# SelfBus_DAP_Debugger.net
KiCad netlist of a schematic drawn in EAGLE
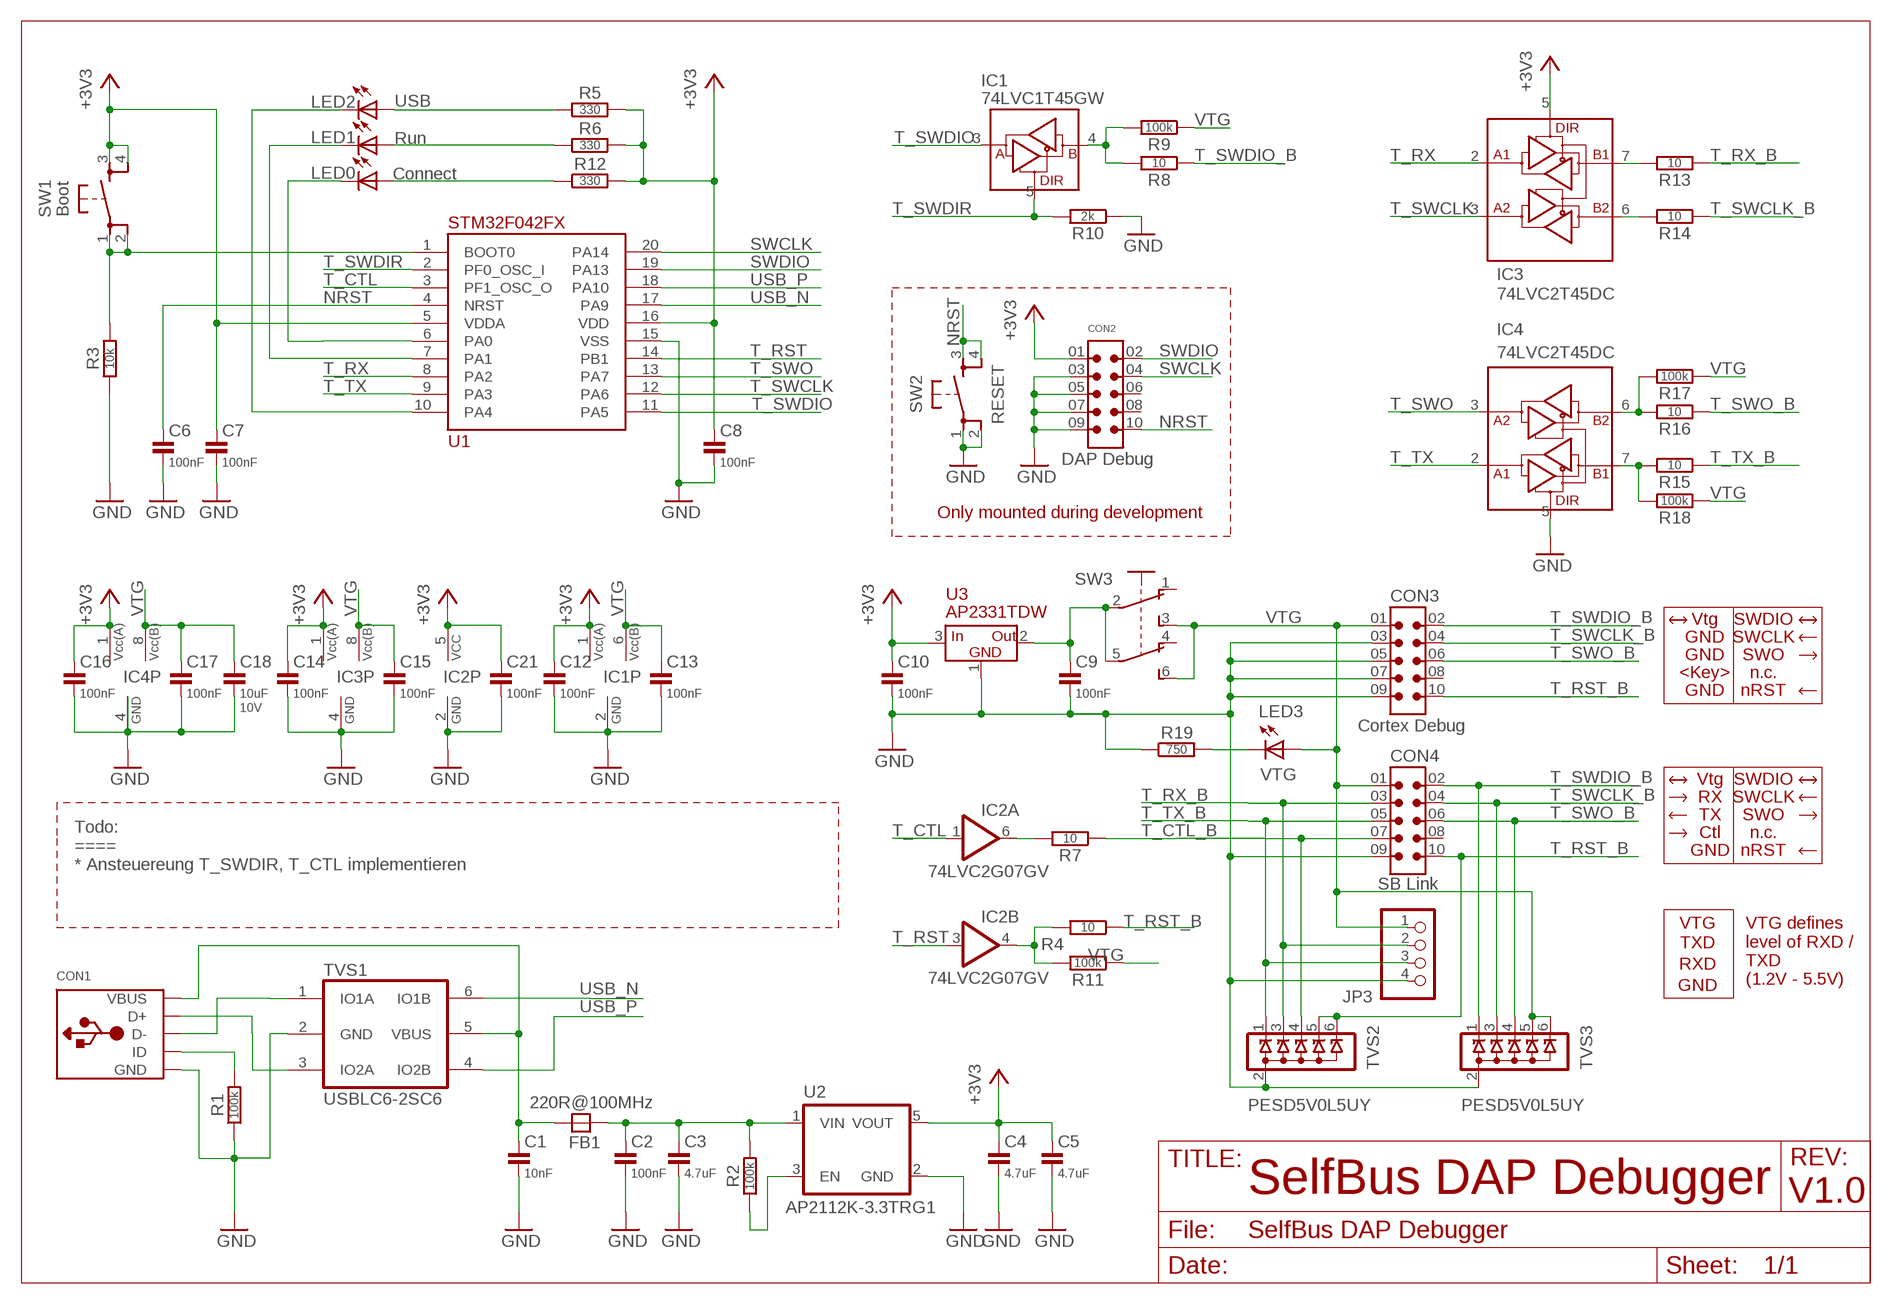
[diagram p0: schematic, sheet 1]

(export (version "E")
  (design (tool "Eeschema 10.0.6"))
  (components
    (comp (ref "C1")
      (value "10nF")
      (footprint "eagle-import:C0805")
      (libsource (lib "eagle-import") (part "C-EUC0805"))
    )
    (comp (ref "C2")
      (value "100nF")
      (footprint "eagle-import:C0805")
      (libsource (lib "eagle-import") (part "C-EUC0805"))
    )
    (comp (ref "C3")
      (value "4.7uF")
      (footprint "eagle-import:C0805")
      (libsource (lib "eagle-import") (part "C-EUC0805"))
    )
    (comp (ref "C4")
      (value "4.7uF")
      (footprint "eagle-import:C0805")
      (libsource (lib "eagle-import") (part "C-EUC0805"))
    )
    (comp (ref "C5")
      (value "4.7uF")
      (footprint "eagle-import:C0805")
      (libsource (lib "eagle-import") (part "C-EUC0805"))
    )
    (comp (ref "C6")
      (value "100nF")
      (footprint "eagle-import:C0805")
      (libsource (lib "eagle-import") (part "C-EUC0805"))
    )
    (comp (ref "C7")
      (value "100nF")
      (footprint "eagle-import:C0805")
      (libsource (lib "eagle-import") (part "C-EUC0805"))
    )
    (comp (ref "C8")
      (value "100nF")
      (footprint "eagle-import:C0805")
      (libsource (lib "eagle-import") (part "C-EUC0805"))
    )
    (comp (ref "C9")
      (value "100nF")
      (footprint "eagle-import:C0805")
      (libsource (lib "eagle-import") (part "C-EUC0805"))
    )
    (comp (ref "C10")
      (value "100nF")
      (footprint "eagle-import:C0805")
      (libsource (lib "eagle-import") (part "C-EUC0805"))
    )
    (comp (ref "C12")
      (value "100nF")
      (footprint "eagle-import:C0805")
      (libsource (lib "eagle-import") (part "C-EUC0805"))
    )
    (comp (ref "C13")
      (value "100nF")
      (footprint "eagle-import:C0805")
      (libsource (lib "eagle-import") (part "C-EUC0805"))
    )
    (comp (ref "C14")
      (value "100nF")
      (footprint "eagle-import:C0805")
      (libsource (lib "eagle-import") (part "C-EUC0805"))
    )
    (comp (ref "C15")
      (value "100nF")
      (footprint "eagle-import:C0805")
      (libsource (lib "eagle-import") (part "C-EUC0805"))
    )
    (comp (ref "C16")
      (value "100nF")
      (footprint "eagle-import:C0805")
      (libsource (lib "eagle-import") (part "C-EUC0805"))
    )
    (comp (ref "C17")
      (value "100nF")
      (footprint "eagle-import:C0805")
      (libsource (lib "eagle-import") (part "C-EUC0805"))
    )
    (comp (ref "C18")
      (value "10uF")
      (footprint "eagle-import:C0805")
      (fields (field (name "VOLTAGE") "10V"))
      (libsource (lib "eagle-import") (part "C-EUC0805"))
    )
    (comp (ref "C21")
      (value "100nF")
      (footprint "eagle-import:C0805")
      (libsource (lib "eagle-import") (part "C-EUC0805"))
    )
    (comp (ref "CON1")
      (value "MICRO-B_U254-051N-4BH806")
      (footprint "eagle-import:U254-051N-4BH806")
      (libsource (lib "eagle-import") (part "MICRO-B_U254-051N-4BH806"))
    )
    (comp (ref "CON2")
      (value "SHF-105-01-X-D-TH")
      (footprint "eagle-import:SAMTEC_SHF-105-01-X-D-TH")
      (libsource (lib "eagle-import") (part "SHF-105-01-X-D-TH"))
    )
    (comp (ref "CON3")
      (value "SHF-105-01-X-D-TH")
      (footprint "eagle-import:SAMTEC_SHF-105-01-X-D-TH")
      (libsource (lib "eagle-import") (part "SHF-105-01-X-D-TH"))
    )
    (comp (ref "CON4")
      (value "SAMTEC-LTMM-105-02-T-D")
      (footprint "eagle-import:SAMTEC-LTMM-105-02-T-D")
      (libsource (lib "eagle-import") (part "SAMTEC-LTMM-105-02-T-D"))
    )
    (comp (ref "FB1")
      (value "220R@100MHz")
      (footprint "eagle-import:FB0805")
      (fields (field (name "PART#") "MPZ2012S221ATD25"))
      (libsource (lib "eagle-import") (part "FB"))
    )
    (comp (ref "IC1")
      (value "74LVC1T45GW")
      (footprint "eagle-import:SOT363")
      (fields
        (field (name "LCSC#") "C478004")
        (field (name "LCSC#2") "C548484")
        (field (name "LCSC#3") "C9382")
        (field (name "MOUSER#") "771-74LVC1T45GW125")
        (field (name "MOUSER#2") "771-74LVC1T45GWQ100H")
        (field (name "MOUSER#3") "595-74LVC1T45QDCKRQ1")
        (field (name "PART#") "74LVC1T45GW,125")
        (field (name "PART#2") "74LVC1T45GW-Q100H")
        (field (name "PART#3") "SN74LVC1T45DCKR")
        (field (name "PART_MFR") "NXP")
        (field (name "PART_MFR2") "NXP")
        (field (name "PART_MFR3") "TI")
      )
      (libsource (lib "eagle-import") (part "741T45GWLVC"))
    )
    (comp (ref "IC2")
      (value "74LVC2G07GV")
      (footprint "eagle-import:SOT23-6")
      (fields
        (field (name "LCSC#") "C548568")
        (field (name "MOUSER#") "771-LVC2G07GV125")
        (field (name "PART#") "74LVC2G07GV,125")
        (field (name "PART_MFR") "NXP")
      )
      (libsource (lib "eagle-import") (part "742G07GVLVC"))
    )
    (comp (ref "IC3")
      (value "74LVC2T45DC")
      (footprint "eagle-import:VSSOP8(0.5)")
      (fields
        (field (name "LCSC#") "C15741")
        (field (name "LCSC#2") "C139524")
        (field (name "MOUSER#") "595-SN74LVC2T45DCUT")
        (field (name "MOUSER#2") "771-74LVCH2T45DC125")
        (field (name "PART#") "SN74LVC2T45DCU")
        (field (name "PART#2") "74LVCH2T45DC,125")
        (field (name "PART_MFR") "TI")
        (field (name "PART_MFR2") "NXP")
      )
      (libsource (lib "eagle-import") (part "742T45DCLVC"))
    )
    (comp (ref "IC4")
      (value "74LVC2T45DC")
      (footprint "eagle-import:VSSOP8(0.5)")
      (libsource (lib "eagle-import") (part "742T45DCLVC"))
    )
    (comp (ref "JP3")
      (value "PINHD-1X4")
      (footprint "eagle-import:1X04")
      (libsource (lib "eagle-import") (part "PINHD-1X4"))
    )
    (comp (ref "LED0")
      (value "Connect")
      (footprint "eagle-import:LED_3MM_GREEN")
      (libsource (lib "eagle-import") (part "LED_3MM(T1)_GREEN"))
    )
    (comp (ref "LED1")
      (value "Run")
      (footprint "eagle-import:LED_3MM_YELLOW")
      (libsource (lib "eagle-import") (part "LED_3MM(T1)_YELLOW"))
    )
    (comp (ref "LED2")
      (value "USB")
      (footprint "eagle-import:LED_3MM_GREEN")
      (libsource (lib "eagle-import") (part "LED_3MM(T1)_GREEN"))
    )
    (comp (ref "LED3")
      (value "VTG")
      (footprint "eagle-import:LED_3MM_RED")
      (libsource (lib "eagle-import") (part "LED_3MM(T1)_RED"))
    )
    (comp (ref "R1")
      (value "100k")
      (footprint "eagle-import:R0805")
      (libsource (lib "eagle-import") (part "R-EU_R0805"))
    )
    (comp (ref "R2")
      (value "100k")
      (footprint "eagle-import:R0805")
      (libsource (lib "eagle-import") (part "R-EU_R0805"))
    )
    (comp (ref "R3")
      (value "10k")
      (footprint "eagle-import:R0805")
      (libsource (lib "eagle-import") (part "R-EU_R0805"))
    )
    (comp (ref "R4")
      (value "10")
      (footprint "eagle-import:R0805")
      (libsource (lib "eagle-import") (part "R-EU_R0805"))
    )
    (comp (ref "R5")
      (value "330")
      (footprint "eagle-import:R0805")
      (libsource (lib "eagle-import") (part "R-EU_R0805"))
    )
    (comp (ref "R6")
      (value "330")
      (footprint "eagle-import:R0805")
      (libsource (lib "eagle-import") (part "R-EU_R0805"))
    )
    (comp (ref "R7")
      (value "10")
      (footprint "eagle-import:R0805")
      (libsource (lib "eagle-import") (part "R-EU_R0805"))
    )
    (comp (ref "R8")
      (value "10")
      (footprint "eagle-import:R0805")
      (libsource (lib "eagle-import") (part "R-EU_R0805"))
    )
    (comp (ref "R9")
      (value "100k")
      (footprint "eagle-import:R0805")
      (libsource (lib "eagle-import") (part "R-EU_R0805"))
    )
    (comp (ref "R10")
      (value "2k")
      (footprint "eagle-import:R0805")
      (libsource (lib "eagle-import") (part "R-EU_R0805"))
    )
    (comp (ref "R11")
      (value "100k")
      (footprint "eagle-import:R0805")
      (libsource (lib "eagle-import") (part "R-EU_R0805"))
    )
    (comp (ref "R12")
      (value "330")
      (footprint "eagle-import:R0805")
      (libsource (lib "eagle-import") (part "R-EU_R0805"))
    )
    (comp (ref "R13")
      (value "10")
      (footprint "eagle-import:R0805")
      (libsource (lib "eagle-import") (part "R-EU_R0805"))
    )
    (comp (ref "R14")
      (value "10")
      (footprint "eagle-import:R0805")
      (libsource (lib "eagle-import") (part "R-EU_R0805"))
    )
    (comp (ref "R15")
      (value "10")
      (footprint "eagle-import:R0805")
      (libsource (lib "eagle-import") (part "R-EU_R0805"))
    )
    (comp (ref "R16")
      (value "10")
      (footprint "eagle-import:R0805")
      (libsource (lib "eagle-import") (part "R-EU_R0805"))
    )
    (comp (ref "R17")
      (value "100k")
      (footprint "eagle-import:R0805")
      (libsource (lib "eagle-import") (part "R-EU_R0805"))
    )
    (comp (ref "R18")
      (value "100k")
      (footprint "eagle-import:R0805")
      (libsource (lib "eagle-import") (part "R-EU_R0805"))
    )
    (comp (ref "R19")
      (value "750")
      (footprint "eagle-import:R0805")
      (libsource (lib "eagle-import") (part "R-EU_R0805"))
    )
    (comp (ref "SW1")
      (value "BOOT")
      (footprint "eagle-import:TACT_SWITCH_6X6_SNAP-IN_17")
      (fields (field (name "PART#") "SKHHDHA010"))
      (libsource (lib "eagle-import") (part "ALPS_SKHHDHA010"))
    )
    (comp (ref "SW2")
      (value "RESET")
      (footprint "eagle-import:TACT_SWITCH_6X6_SNAP-IN_17")
      (fields (field (name "PART#") "SKHHDHA010"))
      (libsource (lib "eagle-import") (part "ALPS_SKHHDHA010"))
    )
    (comp (ref "SW3")
      (value "XKB7070-Z")
      (footprint "eagle-import:XKB7070")
      (libsource (lib "eagle-import") (part "XKB7070-Z"))
    )
    (comp (ref "TVS1")
      (value "USBLC6-2SC6")
      (footprint "eagle-import:SOT-23-6L")
      (libsource (lib "eagle-import") (part "USBLC6-2SC6"))
    )
    (comp (ref "TVS2")
      (value "PESD5V0L5UY")
      (footprint "eagle-import:SOT363")
      (libsource (lib "eagle-import") (part "PESD5V0L5UY"))
    )
    (comp (ref "TVS3")
      (value "PESD5V0L5UY")
      (footprint "eagle-import:SOT363")
      (libsource (lib "eagle-import") (part "PESD5V0L5UY"))
    )
    (comp (ref "U1")
      (value "STM32F042FX")
      (footprint "eagle-import:TSSOP20")
      (fields (field (name "PART#") "STM32F042F4P6"))
      (libsource (lib "eagle-import") (part "STM32F042FX"))
    )
    (comp (ref "U2")
      (value "AP2112K-3.3TRG1")
      (footprint "eagle-import:SOT23-5")
      (libsource (lib "eagle-import") (part "AP2112K-3.3TRG1"))
    )
    (comp (ref "U3")
      (value "AP2331TDW")
      (footprint "eagle-import:SC59")
      (fields (field (name "PART#") "AP2331W-7"))
      (libsource (lib "eagle-import") (part "AP2331TDW"))
    )
  )
  (nets
    (net (code "1") (name "+3V3") (class "Default")
      (node (ref "C10") (pin "1") (pinfunction "1_1") (pintype "passive"))
      (node (ref "C12") (pin "1") (pinfunction "1_1") (pintype "passive"))
      (node (ref "C14") (pin "1") (pinfunction "1_1") (pintype "passive"))
      (node (ref "C16") (pin "1") (pinfunction "1_1") (pintype "passive"))
      (node (ref "C21") (pin "1") (pinfunction "1_1") (pintype "passive"))
      (node (ref "C4") (pin "1") (pinfunction "1_1") (pintype "passive"))
      (node (ref "C5") (pin "1") (pinfunction "1_1") (pintype "passive"))
      (node (ref "C7") (pin "1") (pinfunction "1_1") (pintype "passive"))
      (node (ref "C8") (pin "1") (pinfunction "1_1") (pintype "passive"))
      (node (ref "CON2") (pin "01") (pinfunction "1_01") (pintype "passive"))
      (node (ref "IC1") (pin "1") (pinfunction "VCC(A)_1") (pintype "power_in"))
      (node (ref "IC2") (pin "5") (pinfunction "VCC_5") (pintype "power_in"))
      (node (ref "IC3") (pin "1") (pinfunction "VCC(A)_1") (pintype "power_in"))
      (node (ref "IC3") (pin "5") (pinfunction "DIR_5") (pintype "input"))
      (node (ref "IC4") (pin "1") (pinfunction "VCC(A)_1") (pintype "power_in"))
      (node (ref "R12") (pin "2") (pinfunction "2_2") (pintype "passive"))
      (node (ref "R5") (pin "2") (pinfunction "2_2") (pintype "passive"))
      (node (ref "R6") (pin "2") (pinfunction "2_2") (pintype "passive"))
      (node (ref "SW1") (pin "3") (pinfunction "3_3") (pintype "passive"))
      (node (ref "SW1") (pin "4") (pinfunction "4_4") (pintype "passive"))
      (node (ref "U1") (pin "16") (pinfunction "VDD_16") (pintype "power_in"))
      (node (ref "U1") (pin "5") (pinfunction "VDDA_5") (pintype "power_in"))
      (node (ref "U2") (pin "5") (pinfunction "VOUT_5") (pintype "passive"))
      (node (ref "U3") (pin "3") (pinfunction "IN_3") (pintype "bidirectional"))
    )
    (net (code "2") (name "/NRST") (class "Default")
      (node (ref "C6") (pin "1") (pinfunction "1_1") (pintype "passive"))
      (node (ref "CON2") (pin "10") (pinfunction "10_10") (pintype "passive"))
      (node (ref "SW2") (pin "3") (pinfunction "3_3") (pintype "passive"))
      (node (ref "SW2") (pin "4") (pinfunction "4_4") (pintype "passive"))
      (node (ref "U1") (pin "4") (pinfunction "NRST_4") (pintype "input"))
    )
    (net (code "3") (name "/SWCLK") (class "Default")
      (node (ref "CON2") (pin "04") (pinfunction "4_04") (pintype "passive"))
      (node (ref "U1") (pin "20") (pinfunction "PA14_20") (pintype "bidirectional"))
    )
    (net (code "4") (name "/SWDIO") (class "Default")
      (node (ref "CON2") (pin "02") (pinfunction "2_02") (pintype "passive"))
      (node (ref "U1") (pin "19") (pinfunction "PA13_19") (pintype "bidirectional"))
    )
    (net (code "5") (name "/T_CTL") (class "Default")
      (node (ref "IC2") (pin "1") (pinfunction "IN_1") (pintype "input"))
      (node (ref "U1") (pin "3") (pinfunction "PF1_OSC_O_3") (pintype "bidirectional"))
    )
    (net (code "6") (name "/T_CTL_B") (class "Default")
      (node (ref "CON4") (pin "07") (pinfunction "7_07") (pintype "passive"))
      (node (ref "R7") (pin "1") (pinfunction "1_1") (pintype "passive"))
      (node (ref "TVS2") (pin "4") (pinfunction "C3_4") (pintype "passive"))
    )
    (net (code "7") (name "/T_RST") (class "Default")
      (node (ref "IC2") (pin "3") (pinfunction "IN_3") (pintype "input"))
      (node (ref "U1") (pin "14") (pinfunction "PB1_14") (pintype "bidirectional"))
    )
    (net (code "8") (name "/T_RST_B") (class "Default")
      (node (ref "CON3") (pin "10") (pinfunction "10_10") (pintype "passive"))
      (node (ref "CON4") (pin "10") (pinfunction "10_10") (pintype "passive"))
      (node (ref "R4") (pin "1") (pinfunction "1_1") (pintype "passive"))
      (node (ref "TVS2") (pin "5") (pinfunction "C4_5") (pintype "passive"))
      (node (ref "TVS2") (pin "6") (pinfunction "C5_6") (pintype "passive"))
    )
    (net (code "9") (name "/T_RX") (class "Default")
      (node (ref "IC3") (pin "2") (pinfunction "A1_2") (pintype "bidirectional"))
      (node (ref "U1") (pin "8") (pinfunction "PA2_8") (pintype "bidirectional"))
    )
    (net (code "10") (name "/T_RX_B") (class "Default")
      (node (ref "CON4") (pin "03") (pinfunction "3_03") (pintype "passive"))
      (node (ref "JP3") (pin "2") (pinfunction "2_2") (pintype "passive"))
      (node (ref "R13") (pin "1") (pinfunction "1_1") (pintype "passive"))
      (node (ref "TVS2") (pin "3") (pinfunction "C2_3") (pintype "passive"))
    )
    (net (code "11") (name "/T_SWCLK") (class "Default")
      (node (ref "IC3") (pin "3") (pinfunction "A2_3") (pintype "bidirectional"))
      (node (ref "U1") (pin "12") (pinfunction "PA6_12") (pintype "bidirectional"))
    )
    (net (code "12") (name "/T_SWCLK_B") (class "Default")
      (node (ref "CON3") (pin "04") (pinfunction "4_04") (pintype "passive"))
      (node (ref "CON4") (pin "04") (pinfunction "4_04") (pintype "passive"))
      (node (ref "R14") (pin "1") (pinfunction "1_1") (pintype "passive"))
      (node (ref "TVS3") (pin "3") (pinfunction "C2_3") (pintype "passive"))
    )
    (net (code "13") (name "/T_SWDIO") (class "Default")
      (node (ref "IC1") (pin "3") (pinfunction "A_3") (pintype "bidirectional"))
      (node (ref "U1") (pin "11") (pinfunction "PA5_11") (pintype "bidirectional"))
    )
    (net (code "14") (name "/T_SWDIO_B") (class "Default")
      (node (ref "CON3") (pin "02") (pinfunction "2_02") (pintype "passive"))
      (node (ref "CON4") (pin "02") (pinfunction "2_02") (pintype "passive"))
      (node (ref "R8") (pin "1") (pinfunction "1_1") (pintype "passive"))
      (node (ref "TVS3") (pin "1") (pinfunction "C1_1") (pintype "passive"))
    )
    (net (code "15") (name "/T_SWDIR") (class "Default")
      (node (ref "IC1") (pin "5") (pinfunction "DIR_5") (pintype "input"))
      (node (ref "R10") (pin "2") (pinfunction "2_2") (pintype "passive"))
      (node (ref "U1") (pin "2") (pinfunction "PF0_OSC_I_2") (pintype "bidirectional"))
    )
    (net (code "16") (name "/T_SWO") (class "Default")
      (node (ref "IC4") (pin "3") (pinfunction "A2_3") (pintype "bidirectional"))
      (node (ref "U1") (pin "13") (pinfunction "PA7_13") (pintype "bidirectional"))
    )
    (net (code "17") (name "/T_SWO_B") (class "Default")
      (node (ref "CON3") (pin "06") (pinfunction "6_06") (pintype "passive"))
      (node (ref "CON4") (pin "06") (pinfunction "6_06") (pintype "passive"))
      (node (ref "R16") (pin "1") (pinfunction "1_1") (pintype "passive"))
      (node (ref "TVS3") (pin "4") (pinfunction "C3_4") (pintype "passive"))
    )
    (net (code "18") (name "/T_TX") (class "Default")
      (node (ref "IC4") (pin "2") (pinfunction "A1_2") (pintype "bidirectional"))
      (node (ref "U1") (pin "9") (pinfunction "PA3_9") (pintype "bidirectional"))
    )
    (net (code "19") (name "/T_TX_B") (class "Default")
      (node (ref "CON4") (pin "05") (pinfunction "5_05") (pintype "passive"))
      (node (ref "JP3") (pin "3") (pinfunction "3_3") (pintype "passive"))
      (node (ref "R15") (pin "1") (pinfunction "1_1") (pintype "passive"))
      (node (ref "TVS2") (pin "1") (pinfunction "C1_1") (pintype "passive"))
    )
    (net (code "20") (name "/USB_N") (class "Default")
      (node (ref "TVS1") (pin "6") (pinfunction "IO1B_6") (pintype "bidirectional"))
      (node (ref "U1") (pin "17") (pinfunction "PA9_17") (pintype "bidirectional"))
    )
    (net (code "21") (name "/USB_P") (class "Default")
      (node (ref "TVS1") (pin "4") (pinfunction "IO2B_4") (pintype "bidirectional"))
      (node (ref "U1") (pin "18") (pinfunction "PA10_18") (pintype "bidirectional"))
    )
    (net (code "22") (name "/VTG") (class "Default")
      (node (ref "C13") (pin "1") (pinfunction "1_1") (pintype "passive"))
      (node (ref "C15") (pin "1") (pinfunction "1_1") (pintype "passive"))
      (node (ref "C17") (pin "1") (pinfunction "1_1") (pintype "passive"))
      (node (ref "C18") (pin "1") (pinfunction "1_1") (pintype "passive"))
      (node (ref "CON3") (pin "01") (pinfunction "1_01") (pintype "passive"))
      (node (ref "CON4") (pin "01") (pinfunction "1_01") (pintype "passive"))
      (node (ref "IC1") (pin "6") (pinfunction "VCC(B)_6") (pintype "power_in"))
      (node (ref "IC3") (pin "8") (pinfunction "VCC(B)_8") (pintype "power_in"))
      (node (ref "IC4") (pin "8") (pinfunction "VCC(B)_8") (pintype "power_in"))
      (node (ref "JP3") (pin "1") (pinfunction "1_1") (pintype "passive"))
      (node (ref "LED3") (pin "A") (pinfunction "A_A") (pintype "passive"))
      (node (ref "R11") (pin "1") (pinfunction "1_1") (pintype "passive"))
      (node (ref "R17") (pin "1") (pinfunction "1_1") (pintype "passive"))
      (node (ref "R18") (pin "1") (pinfunction "1_1") (pintype "passive"))
      (node (ref "R9") (pin "1") (pinfunction "1_1") (pintype "passive"))
      (node (ref "SW3") (pin "3") (pinfunction "S_3") (pintype "passive"))
      (node (ref "SW3") (pin "6") (pinfunction "S_6") (pintype "passive"))
      (node (ref "TVS3") (pin "5") (pinfunction "C4_5") (pintype "passive"))
      (node (ref "TVS3") (pin "6") (pinfunction "C5_6") (pintype "passive"))
    )
    (net (code "23") (name "GND") (class "Default")
      (node (ref "C1") (pin "2") (pinfunction "2_2") (pintype "passive"))
      (node (ref "C10") (pin "2") (pinfunction "2_2") (pintype "passive"))
      (node (ref "C12") (pin "2") (pinfunction "2_2") (pintype "passive"))
      (node (ref "C13") (pin "2") (pinfunction "2_2") (pintype "passive"))
      (node (ref "C14") (pin "2") (pinfunction "2_2") (pintype "passive"))
      (node (ref "C15") (pin "2") (pinfunction "2_2") (pintype "passive"))
      (node (ref "C16") (pin "2") (pinfunction "2_2") (pintype "passive"))
      (node (ref "C17") (pin "2") (pinfunction "2_2") (pintype "passive"))
      (node (ref "C18") (pin "2") (pinfunction "2_2") (pintype "passive"))
      (node (ref "C2") (pin "2") (pinfunction "2_2") (pintype "passive"))
      (node (ref "C21") (pin "2") (pinfunction "2_2") (pintype "passive"))
      (node (ref "C3") (pin "2") (pinfunction "2_2") (pintype "passive"))
      (node (ref "C4") (pin "2") (pinfunction "2_2") (pintype "passive"))
      (node (ref "C5") (pin "2") (pinfunction "2_2") (pintype "passive"))
      (node (ref "C6") (pin "2") (pinfunction "2_2") (pintype "passive"))
      (node (ref "C7") (pin "2") (pinfunction "2_2") (pintype "passive"))
      (node (ref "C8") (pin "2") (pinfunction "2_2") (pintype "passive"))
      (node (ref "C9") (pin "2") (pinfunction "2_2") (pintype "passive"))
      (node (ref "CON1") (pin "GND") (pinfunction "GND_GND") (pintype "bidirectional"))
      (node (ref "CON1") (pin "SCR@1") (pinfunction "GND_SCR@1") (pintype "bidirectional"))
      (node (ref "CON1") (pin "SCR@2") (pinfunction "GND_SCR@2") (pintype "bidirectional"))
      (node (ref "CON1") (pin "SCR@3") (pinfunction "GND_SCR@3") (pintype "bidirectional"))
      (node (ref "CON1") (pin "SCR@4") (pinfunction "GND_SCR@4") (pintype "bidirectional"))
      (node (ref "CON2") (pin "03") (pinfunction "3_03") (pintype "passive"))
      (node (ref "CON2") (pin "05") (pinfunction "5_05") (pintype "passive"))
      (node (ref "CON2") (pin "07") (pinfunction "7_07") (pintype "passive"))
      (node (ref "CON2") (pin "09") (pinfunction "9_09") (pintype "passive"))
      (node (ref "CON3") (pin "03") (pinfunction "3_03") (pintype "passive"))
      (node (ref "CON3") (pin "05") (pinfunction "5_05") (pintype "passive"))
      (node (ref "CON3") (pin "07") (pinfunction "7_07") (pintype "passive"))
      (node (ref "CON3") (pin "09") (pinfunction "9_09") (pintype "passive"))
      (node (ref "CON4") (pin "09") (pinfunction "9_09") (pintype "passive"))
      (node (ref "IC1") (pin "2") (pinfunction "GND_2") (pintype "power_in"))
      (node (ref "IC2") (pin "2") (pinfunction "GND_2") (pintype "power_in"))
      (node (ref "IC3") (pin "4") (pinfunction "GND_4") (pintype "power_in"))
      (node (ref "IC4") (pin "4") (pinfunction "GND_4") (pintype "power_in"))
      (node (ref "IC4") (pin "5") (pinfunction "DIR_5") (pintype "input"))
      (node (ref "JP3") (pin "4") (pinfunction "4_4") (pintype "passive"))
      (node (ref "R1") (pin "1") (pinfunction "1_1") (pintype "passive"))
      (node (ref "R10") (pin "1") (pinfunction "1_1") (pintype "passive"))
      (node (ref "R19") (pin "1") (pinfunction "1_1") (pintype "passive"))
      (node (ref "R3") (pin "1") (pinfunction "1_1") (pintype "passive"))
      (node (ref "SW2") (pin "1") (pinfunction "1_1") (pintype "passive"))
      (node (ref "SW2") (pin "2") (pinfunction "2_2") (pintype "passive"))
      (node (ref "TVS1") (pin "2") (pinfunction "GND_2") (pintype "bidirectional"))
      (node (ref "TVS2") (pin "2") (pinfunction "A_2") (pintype "passive"))
      (node (ref "TVS3") (pin "2") (pinfunction "A_2") (pintype "passive"))
      (node (ref "U1") (pin "15") (pinfunction "VSS_15") (pintype "power_in"))
      (node (ref "U2") (pin "2") (pinfunction "GND_2") (pintype "input"))
      (node (ref "U3") (pin "1") (pinfunction "GND_1") (pintype "bidirectional"))
    )
    (net (code "24") (name "Net-(CON1-PadID)") (class "Default")
      (node (ref "CON1") (pin "ID") (pinfunction "ID_ID") (pintype "bidirectional"))
      (node (ref "R1") (pin "2") (pinfunction "2_2") (pintype "passive"))
    )
    (net (code "25") (name "Net-(IC1A-B)") (class "Default")
      (node (ref "IC1") (pin "4") (pinfunction "B_4") (pintype "tri_state"))
      (node (ref "R8") (pin "2") (pinfunction "2_2") (pintype "passive"))
      (node (ref "R9") (pin "2") (pinfunction "2_2") (pintype "passive"))
    )
    (net (code "26") (name "Net-(IC2A-OUT)") (class "Default")
      (node (ref "IC2") (pin "6") (pinfunction "OUT_6") (pintype "open_collector"))
      (node (ref "R7") (pin "2") (pinfunction "2_2") (pintype "passive"))
    )
    (net (code "27") (name "Net-(IC2B-OUT)") (class "Default")
      (node (ref "IC2") (pin "4") (pinfunction "OUT_4") (pintype "open_collector"))
      (node (ref "R11") (pin "2") (pinfunction "2_2") (pintype "passive"))
      (node (ref "R4") (pin "2") (pinfunction "2_2") (pintype "passive"))
    )
    (net (code "28") (name "Net-(IC3A-B1)") (class "Default")
      (node (ref "IC3") (pin "7") (pinfunction "B1_7") (pintype "tri_state"))
      (node (ref "R13") (pin "2") (pinfunction "2_2") (pintype "passive"))
    )
    (net (code "29") (name "Net-(IC3A-B2)") (class "Default")
      (node (ref "IC3") (pin "6") (pinfunction "B2_6") (pintype "tri_state"))
      (node (ref "R14") (pin "2") (pinfunction "2_2") (pintype "passive"))
    )
    (net (code "30") (name "Net-(IC4A-B1)") (class "Default")
      (node (ref "IC4") (pin "7") (pinfunction "B1_7") (pintype "tri_state"))
      (node (ref "R15") (pin "2") (pinfunction "2_2") (pintype "passive"))
      (node (ref "R18") (pin "2") (pinfunction "2_2") (pintype "passive"))
    )
    (net (code "31") (name "Net-(IC4A-B2)") (class "Default")
      (node (ref "IC4") (pin "6") (pinfunction "B2_6") (pintype "tri_state"))
      (node (ref "R16") (pin "2") (pinfunction "2_2") (pintype "passive"))
      (node (ref "R17") (pin "2") (pinfunction "2_2") (pintype "passive"))
    )
    (net (code "32") (name "Net-(LED0-PadA)") (class "Default")
      (node (ref "LED0") (pin "A") (pinfunction "A_A") (pintype "passive"))
      (node (ref "R12") (pin "1") (pinfunction "1_1") (pintype "passive"))
    )
    (net (code "33") (name "Net-(LED1-PadA)") (class "Default")
      (node (ref "LED1") (pin "A") (pinfunction "A_A") (pintype "passive"))
      (node (ref "R6") (pin "1") (pinfunction "1_1") (pintype "passive"))
    )
    (net (code "34") (name "Net-(LED2-PadA)") (class "Default")
      (node (ref "LED2") (pin "A") (pinfunction "A_A") (pintype "passive"))
      (node (ref "R5") (pin "1") (pinfunction "1_1") (pintype "passive"))
    )
    (net (code "35") (name "Net-(LED3-PadC)") (class "Default")
      (node (ref "LED3") (pin "C") (pinfunction "C_C") (pintype "passive"))
      (node (ref "R19") (pin "2") (pinfunction "2_2") (pintype "passive"))
    )
    (net (code "36") (name "Net-(SW3A-P)") (class "Default")
      (node (ref "C9") (pin "1") (pinfunction "1_1") (pintype "passive"))
      (node (ref "SW3") (pin "2") (pinfunction "P_2") (pintype "passive"))
      (node (ref "SW3") (pin "5") (pinfunction "P_5") (pintype "passive"))
      (node (ref "U3") (pin "2") (pinfunction "OUT_2") (pintype "bidirectional"))
    )
    (net (code "37") (name "Net-(TVS1-IO1A)") (class "Default")
      (node (ref "CON1") (pin "D-") (pinfunction "D-_D-") (pintype "bidirectional"))
      (node (ref "TVS1") (pin "1") (pinfunction "IO1A_1") (pintype "bidirectional"))
    )
    (net (code "38") (name "Net-(TVS1-IO2A)") (class "Default")
      (node (ref "CON1") (pin "D+") (pinfunction "D+_D+") (pintype "bidirectional"))
      (node (ref "TVS1") (pin "3") (pinfunction "IO2A_3") (pintype "bidirectional"))
    )
    (net (code "39") (name "Net-(TVS1-VBUS)") (class "Default")
      (node (ref "C1") (pin "1") (pinfunction "1_1") (pintype "passive"))
      (node (ref "CON1") (pin "VBUS") (pinfunction "VBUS_VBUS") (pintype "bidirectional"))
      (node (ref "FB1") (pin "1") (pinfunction "1_1") (pintype "passive"))
      (node (ref "TVS1") (pin "5") (pinfunction "VBUS_5") (pintype "bidirectional"))
    )
    (net (code "40") (name "Net-(U1-BOOT0)") (class "Default")
      (node (ref "R3") (pin "2") (pinfunction "2_2") (pintype "passive"))
      (node (ref "SW1") (pin "1") (pinfunction "1_1") (pintype "passive"))
      (node (ref "SW1") (pin "2") (pinfunction "2_2") (pintype "passive"))
      (node (ref "U1") (pin "1") (pinfunction "BOOT0_1") (pintype "bidirectional"))
    )
    (net (code "41") (name "Net-(U1-PA0)") (class "Default")
      (node (ref "LED0") (pin "C") (pinfunction "C_C") (pintype "passive"))
      (node (ref "U1") (pin "6") (pinfunction "PA0_6") (pintype "bidirectional"))
    )
    (net (code "42") (name "Net-(U1-PA1)") (class "Default")
      (node (ref "LED1") (pin "C") (pinfunction "C_C") (pintype "passive"))
      (node (ref "U1") (pin "7") (pinfunction "PA1_7") (pintype "bidirectional"))
    )
    (net (code "43") (name "Net-(U1-PA4)") (class "Default")
      (node (ref "LED2") (pin "C") (pinfunction "C_C") (pintype "passive"))
      (node (ref "U1") (pin "10") (pinfunction "PA4_10") (pintype "bidirectional"))
    )
    (net (code "44") (name "Net-(U2-EN)") (class "Default")
      (node (ref "R2") (pin "1") (pinfunction "1_1") (pintype "passive"))
      (node (ref "U2") (pin "3") (pinfunction "EN_3") (pintype "input"))
    )
    (net (code "45") (name "Net-(U2-VIN)") (class "Default")
      (node (ref "C2") (pin "1") (pinfunction "1_1") (pintype "passive"))
      (node (ref "C3") (pin "1") (pinfunction "1_1") (pintype "passive"))
      (node (ref "FB1") (pin "2") (pinfunction "2_2") (pintype "passive"))
      (node (ref "R2") (pin "2") (pinfunction "2_2") (pintype "passive"))
      (node (ref "U2") (pin "1") (pinfunction "VIN_1") (pintype "input"))
    )
    (net (code "46") (name "unconnected-(CON2-6-Pad06)") (class "Default")
      (node (ref "CON2") (pin "06") (pinfunction "6_06") (pintype "passive"))
    )
    (net (code "47") (name "unconnected-(CON2-8-Pad08)") (class "Default")
      (node (ref "CON2") (pin "08") (pinfunction "8_08") (pintype "passive"))
    )
    (net (code "48") (name "unconnected-(CON3-8-Pad08)") (class "Default")
      (node (ref "CON3") (pin "08") (pinfunction "8_08") (pintype "passive"))
    )
    (net (code "49") (name "unconnected-(CON4-8-Pad08)") (class "Default")
      (node (ref "CON4") (pin "08") (pinfunction "8_08") (pintype "passive"))
    )
    (net (code "50") (name "unconnected-(SW3A-O-Pad1)") (class "Default")
      (node (ref "SW3") (pin "1") (pinfunction "O_1") (pintype "passive"))
    )
    (net (code "51") (name "unconnected-(SW3B-O-Pad4)") (class "Default")
      (node (ref "SW3") (pin "4") (pinfunction "O_4") (pintype "passive"))
    )
  )
)
